# CAN.net
KiCad netlist of a schematic drawn in Altium Designer
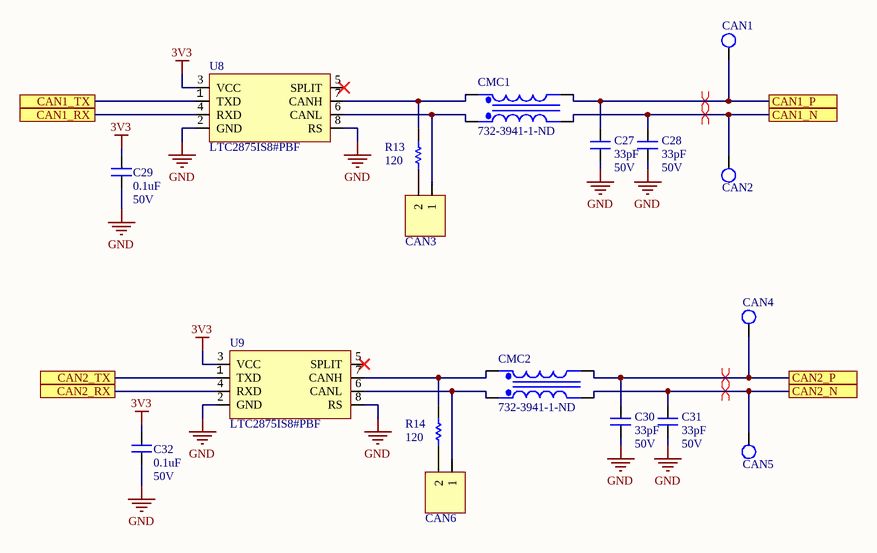
[diagram p0: CAN.SchDoc]

(export (version "E")
  (design (tool "Eeschema 10.0.6"))
  (components
    (comp (ref "C27")
      (value "CAP_33pF_50V_0603")
      (footprint "CAPC0603(1608)55_N")
      (description "CAP CER 33PF 50V C0G/NP0")
      (fields
        (field (name "VOLTAGE") "50V")
        (field (name "TOLERANCE") "5%")
        (field (name "CAPACITANCE") "33pF")
      )
      (libsource (lib "UWRT_Schematic_Library_2020") (part "CAP_33pF_50V_0603"))
    )
    (comp (ref "C28")
      (value "CAP_33pF_50V_0603")
      (footprint "CAPC0603(1608)55_N")
      (description "CAP CER 33PF 50V C0G/NP0")
      (fields
        (field (name "VOLTAGE") "50V")
        (field (name "TOLERANCE") "5%")
        (field (name "CAPACITANCE") "33pF")
      )
      (libsource (lib "UWRT_Schematic_Library_2020") (part "CAP_33pF_50V_0603"))
    )
    (comp (ref "C29")
      (value "0.1uF")
      (footprint "CAPC2012X140N")
      (description "CAP CER 0.1UF 50V X7R 0805")
      (fields
        (field (name "TOLERANCE") "10%")
        (field (name "VOLTAGE RATING") "50V")
        (field (name "Comment") "CAP_0.1uF_50V_0805")
      )
      (libsource (lib "UWRT_Schematic_Library_2020") (part "CAP_0.1uF_50V_0805"))
    )
    (comp (ref "C30")
      (value "CAP_33pF_50V_0603")
      (footprint "CAPC0603(1608)55_N")
      (description "CAP CER 33PF 50V C0G/NP0")
      (fields
        (field (name "VOLTAGE") "50V")
        (field (name "TOLERANCE") "5%")
        (field (name "CAPACITANCE") "33pF")
      )
      (libsource (lib "UWRT_Schematic_Library_2020") (part "CAP_33pF_50V_0603"))
    )
    (comp (ref "C31")
      (value "CAP_33pF_50V_0603")
      (footprint "CAPC0603(1608)55_N")
      (description "CAP CER 33PF 50V C0G/NP0")
      (fields
        (field (name "VOLTAGE") "50V")
        (field (name "TOLERANCE") "5%")
        (field (name "CAPACITANCE") "33pF")
      )
      (libsource (lib "UWRT_Schematic_Library_2020") (part "CAP_33pF_50V_0603"))
    )
    (comp (ref "C32")
      (value "0.1uF")
      (footprint "CAPC2012X140N")
      (description "CAP CER 0.1UF 50V X7R 0805")
      (fields
        (field (name "TOLERANCE") "10%")
        (field (name "VOLTAGE RATING") "50V")
        (field (name "Comment") "CAP_0.1uF_50V_0805")
      )
      (libsource (lib "UWRT_Schematic_Library_2020") (part "CAP_0.1uF_50V_0805"))
    )
    (comp (ref "CAN1")
      (value "TESTPOINT_LOOP")
      (footprint "TESTPOINT_LOOP")
      (description "Loop testpoint through-hole pad")
      (libsource (lib "UWRT_Schematic_Library_2020") (part "TESTPOINT_LOOP"))
    )
    (comp (ref "CAN2")
      (value "TESTPOINT_LOOP")
      (footprint "TESTPOINT_LOOP")
      (description "Loop testpoint through-hole pad")
      (libsource (lib "UWRT_Schematic_Library_2020") (part "TESTPOINT_LOOP"))
    )
    (comp (ref "CAN3")
      (value "JUMPER_2")
      (footprint "HDR1X2")
      (description "HEADER 2X1")
      (libsource (lib "UWRT_Schematic_Library_2020") (part "JUMPER_2"))
    )
    (comp (ref "CAN4")
      (value "TESTPOINT_LOOP")
      (footprint "TESTPOINT_LOOP")
      (description "Loop testpoint through-hole pad")
      (libsource (lib "UWRT_Schematic_Library_2020") (part "TESTPOINT_LOOP"))
    )
    (comp (ref "CAN5")
      (value "TESTPOINT_LOOP")
      (footprint "TESTPOINT_LOOP")
      (description "Loop testpoint through-hole pad")
      (libsource (lib "UWRT_Schematic_Library_2020") (part "TESTPOINT_LOOP"))
    )
    (comp (ref "CAN6")
      (value "JUMPER_2")
      (footprint "HDR1X2")
      (description "HEADER 2X1")
      (libsource (lib "UWRT_Schematic_Library_2020") (part "JUMPER_2"))
    )
    (comp (ref "CMC1")
      (value "CMC_51uH")
      (footprint "744212510")
      (description "CMC 51uH 300MA 2LN SMD")
      (fields (field (name "TOLERANCE") "50%") (field (name "SUPPLIER PART NUMBER 1") "732-3941-1-ND"))
      (libsource (lib "UWRT_Schematic_Library_2020") (part "CMC_51uH"))
    )
    (comp (ref "CMC2")
      (value "CMC_51uH")
      (footprint "744212510")
      (description "CMC 51uH 300MA 2LN SMD")
      (fields (field (name "TOLERANCE") "50%") (field (name "SUPPLIER PART NUMBER 1") "732-3941-1-ND"))
      (libsource (lib "UWRT_Schematic_Library_2020") (part "CMC_51uH"))
    )
    (comp (ref "R13")
      (value "120")
      (footprint "RESC0603(1608)_N")
      (description "RES SMD 120 OHM 5% 1/10W 0603")
      (fields (field (name "TOLERANCE") "5%") (field (name "Comment") "RES_120R_0603"))
      (libsource (lib "UWRT_Schematic_Library_2020") (part "RES_120R_0603"))
    )
    (comp (ref "R14")
      (value "120")
      (footprint "RESC0603(1608)_N")
      (description "RES SMD 120 OHM 5% 1/10W 0603")
      (fields (field (name "TOLERANCE") "5%") (field (name "Comment") "RES_120R_0603"))
      (libsource (lib "UWRT_Schematic_Library_2020") (part "RES_120R_0603"))
    )
    (comp (ref "U8")
      (value "IC TXRX CAN")
      (footprint "LT-S8_N")
      (description "IC TXRX CAN 4MBPS 8SO")
      (fields (field (name "MANUFACTURER PART NUMBER 1") "LTC2875IS8#PBF"))
      (libsource (lib "UWRT_Schematic_Library_2020") (part "LTC2875"))
    )
    (comp (ref "U9")
      (value "IC TXRX CAN")
      (footprint "LT-S8_N")
      (description "IC TXRX CAN 4MBPS 8SO")
      (fields (field (name "MANUFACTURER PART NUMBER 1") "LTC2875IS8#PBF"))
      (libsource (lib "UWRT_Schematic_Library_2020") (part "LTC2875"))
    )
  )
  (nets
    (net (code "1") (name "/CAN1_N") (class "Default")
      (node (ref "C28") (pin "2") (pinfunction "2_2") (pintype "passive"))
      (node (ref "CAN2") (pin "1") (pintype "passive"))
      (node (ref "CMC1") (pin "5") (pinfunction "Pri-_5") (pintype "passive"))
    )
    (net (code "2") (name "/CAN1_P") (class "Default")
      (node (ref "C27") (pin "2") (pinfunction "2_2") (pintype "passive"))
      (node (ref "CAN1") (pin "1") (pintype "passive"))
      (node (ref "CMC1") (pin "4") (pinfunction "Sec-_4") (pintype "passive"))
    )
    (net (code "3") (name "/CAN1_RX") (class "Default")
      (node (ref "U8") (pin "4") (pinfunction "RXD_4") (pintype "passive"))
    )
    (net (code "4") (name "/CAN1_TX") (class "Default")
      (node (ref "U8") (pin "1") (pinfunction "TXD_1") (pintype "passive"))
    )
    (net (code "5") (name "/CAN2_N") (class "Default")
      (node (ref "C31") (pin "2") (pinfunction "2_2") (pintype "passive"))
      (node (ref "CAN5") (pin "1") (pintype "passive"))
      (node (ref "CMC2") (pin "5") (pinfunction "Pri-_5") (pintype "passive"))
    )
    (net (code "6") (name "/CAN2_P") (class "Default")
      (node (ref "C30") (pin "2") (pinfunction "2_2") (pintype "passive"))
      (node (ref "CAN4") (pin "1") (pintype "passive"))
      (node (ref "CMC2") (pin "4") (pinfunction "Sec-_4") (pintype "passive"))
    )
    (net (code "7") (name "/CAN2_RX") (class "Default")
      (node (ref "U9") (pin "4") (pinfunction "RXD_4") (pintype "passive"))
    )
    (net (code "8") (name "/CAN2_TX") (class "Default")
      (node (ref "U9") (pin "1") (pinfunction "TXD_1") (pintype "passive"))
    )
    (net (code "9") (name "3V3") (class "Default")
      (node (ref "C29") (pin "2") (pinfunction "2_2") (pintype "passive"))
      (node (ref "C32") (pin "2") (pinfunction "2_2") (pintype "passive"))
      (node (ref "U8") (pin "3") (pinfunction "VCC_3") (pintype "passive"))
      (node (ref "U9") (pin "3") (pinfunction "VCC_3") (pintype "passive"))
    )
    (net (code "10") (name "GND") (class "Default")
      (node (ref "C27") (pin "1") (pinfunction "1_1") (pintype "passive"))
      (node (ref "C28") (pin "1") (pinfunction "1_1") (pintype "passive"))
      (node (ref "C29") (pin "1") (pinfunction "1_1") (pintype "passive"))
      (node (ref "C30") (pin "1") (pinfunction "1_1") (pintype "passive"))
      (node (ref "C31") (pin "1") (pinfunction "1_1") (pintype "passive"))
      (node (ref "C32") (pin "1") (pinfunction "1_1") (pintype "passive"))
      (node (ref "U8") (pin "2") (pinfunction "GND_2") (pintype "passive"))
      (node (ref "U8") (pin "8") (pinfunction "RS_8") (pintype "passive"))
      (node (ref "U9") (pin "2") (pinfunction "GND_2") (pintype "passive"))
      (node (ref "U9") (pin "8") (pinfunction "RS_8") (pintype "passive"))
    )
    (net (code "11") (name "Net-(CAN3-Pad2)") (class "Default")
      (node (ref "CAN3") (pin "2") (pinfunction "2_2") (pintype "passive"))
      (node (ref "R13") (pin "2") (pinfunction "2_2") (pintype "passive"))
    )
    (net (code "12") (name "Net-(CAN6-Pad2)") (class "Default")
      (node (ref "CAN6") (pin "2") (pinfunction "2_2") (pintype "passive"))
      (node (ref "R14") (pin "2") (pinfunction "2_2") (pintype "passive"))
    )
    (net (code "13") (name "Net-(CMC1-Pri+)") (class "Default")
      (node (ref "CAN3") (pin "1") (pinfunction "1_1") (pintype "passive"))
      (node (ref "CMC1") (pin "1") (pinfunction "Pri+_1") (pintype "passive"))
      (node (ref "U8") (pin "6") (pinfunction "CANL_6") (pintype "passive"))
    )
    (net (code "14") (name "Net-(CMC1-Sec+)") (class "Default")
      (node (ref "CMC1") (pin "3") (pinfunction "Sec+_3") (pintype "passive"))
      (node (ref "R13") (pin "1") (pinfunction "1_1") (pintype "passive"))
      (node (ref "U8") (pin "7") (pinfunction "CANH_7") (pintype "passive"))
    )
    (net (code "15") (name "Net-(CMC2-Pri+)") (class "Default")
      (node (ref "CAN6") (pin "1") (pinfunction "1_1") (pintype "passive"))
      (node (ref "CMC2") (pin "1") (pinfunction "Pri+_1") (pintype "passive"))
      (node (ref "U9") (pin "6") (pinfunction "CANL_6") (pintype "passive"))
    )
    (net (code "16") (name "Net-(CMC2-Sec+)") (class "Default")
      (node (ref "CMC2") (pin "3") (pinfunction "Sec+_3") (pintype "passive"))
      (node (ref "R14") (pin "1") (pinfunction "1_1") (pintype "passive"))
      (node (ref "U9") (pin "7") (pinfunction "CANH_7") (pintype "passive"))
    )
    (net (code "17") (name "unconnected-(U8-SPLIT-Pad5)") (class "Default")
      (node (ref "U8") (pin "5") (pinfunction "SPLIT_5") (pintype "passive+no_connect"))
    )
    (net (code "18") (name "unconnected-(U9-SPLIT-Pad5)") (class "Default")
      (node (ref "U9") (pin "5") (pinfunction "SPLIT_5") (pintype "passive+no_connect"))
    )
  )
)
